# Mesh.net
KiCad netlist of a schematic drawn in EAGLE
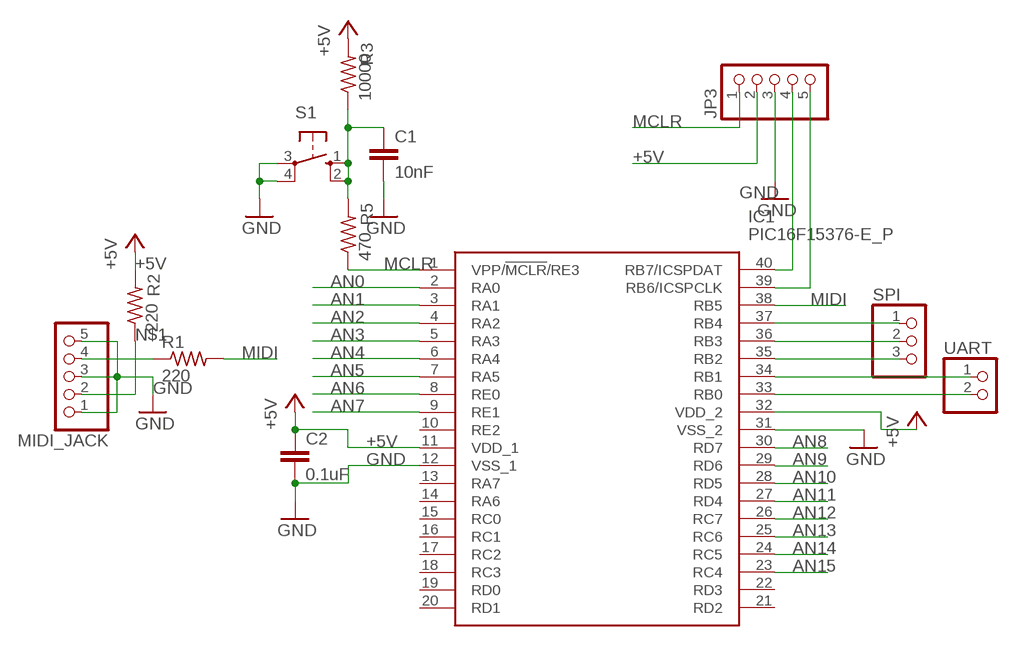
[diagram p0: schematic, sheet 1]
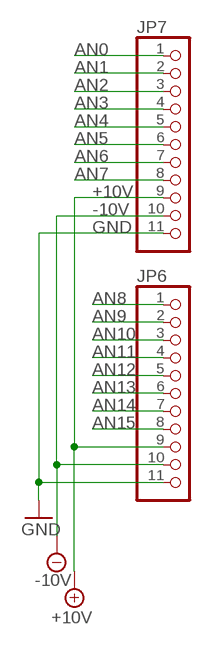
[diagram p1: schematic, sheet 2]
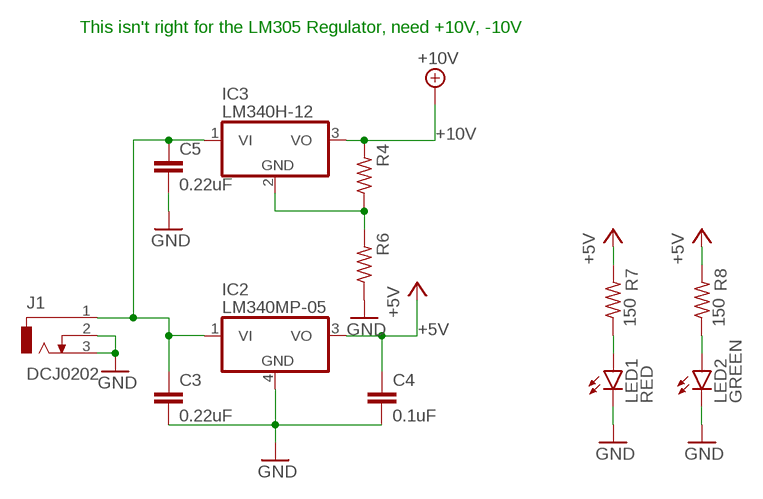
[diagram p2: schematic, sheet 3]
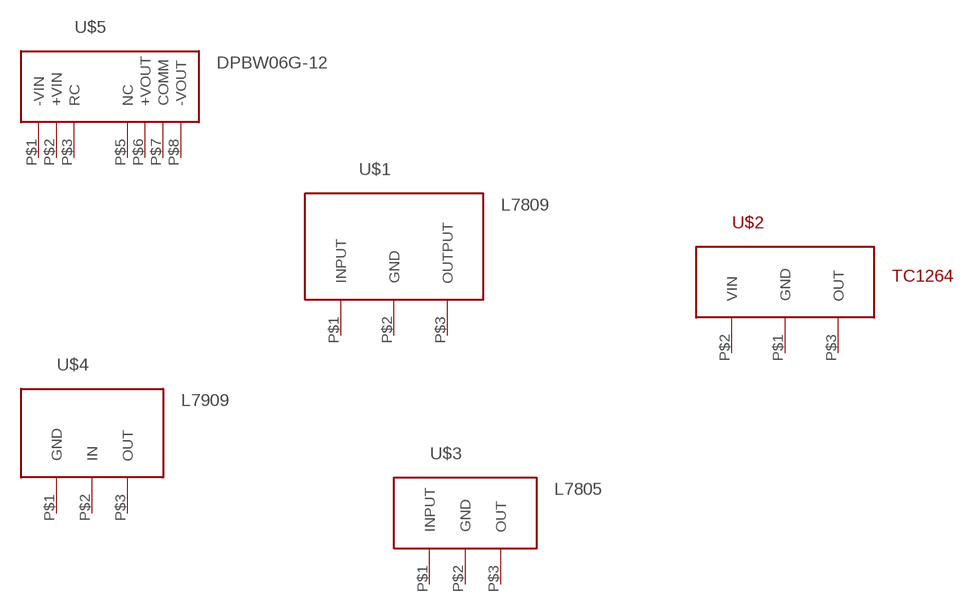
[diagram p3: schematic, sheet 4]

(export (version "E")
  (design (tool "Eeschema 10.0.6"))
  (components
    (comp (ref "JP6")
      (value "PINHD-1X11/90")
      (footprint "eagle-import:1X11_90")
      (libsource (lib "eagle-import") (part "PINHD-1X11/90"))
    )
    (comp (ref "JP7")
      (value "PINHD-1X11/90")
      (footprint "eagle-import:1X11_90")
      (libsource (lib "eagle-import") (part "PINHD-1X11/90"))
    )
    (comp (ref "U$1")
      (value "L7809")
      (footprint "eagle-import:L7809")
      (libsource (lib "eagle-import") (part "L7809"))
    )
    (comp (ref "U$2")
      (value "TC1264")
      (footprint "eagle-import:TC1264")
      (libsource (lib "eagle-import") (part "TC1264"))
    )
    (comp (ref "U$3")
      (value "L7805")
      (footprint "eagle-import:L7805")
      (libsource (lib "eagle-import") (part "L7805"))
    )
    (comp (ref "U$4")
      (value "L7909")
      (footprint "eagle-import:L7909")
      (libsource (lib "eagle-import") (part "L7909"))
    )
    (comp (ref "U$5")
      (value "DPBW06G-12")
      (footprint "eagle-import:DPBW06G-12")
      (libsource (lib "eagle-import") (part "DPBW06G-12"))
    )
    (comp (ref "C1")
      (value "10nF")
      (footprint "eagle-import:C0603")
      (libsource (lib "eagle-import") (part "C-EUC0603"))
    )
    (comp (ref "C2")
      (value "0.1uF")
      (footprint "eagle-import:C0603")
      (libsource (lib "eagle-import") (part "C-EUC0603"))
    )
    (comp (ref "IC1")
      (value "PIC16F15376-E_P")
      (footprint "eagle-import:DIP1543W58P254L5175H635Q40N")
      (fields
        (field (name "MANUFACTURER_PART_NUMBER") "PIC16F15376-E/P")
        (field (name "MOUSER_PART_NUMBER") "579-PIC16F15376-E/P")
      )
      (libsource (lib "eagle-import") (part "PIC16F15376-E_P"))
    )
    (comp (ref "JP3")
      (value "PINHD-1X5")
      (footprint "eagle-import:1X05")
      (libsource (lib "eagle-import") (part "PINHD-1X5"))
    )
    (comp (ref "MIDI_JACK")
      (value "PINHD-1X5")
      (footprint "eagle-import:1X05")
      (libsource (lib "eagle-import") (part "PINHD-1X5"))
    )
    (comp (ref "R1")
      (value "220")
      (footprint "eagle-import:R0603")
      (libsource (lib "eagle-import") (part "R-US_R0603"))
    )
    (comp (ref "R2")
      (value "220")
      (footprint "eagle-import:R0603")
      (libsource (lib "eagle-import") (part "R-US_R0603"))
    )
    (comp (ref "R3")
      (value "10000")
      (footprint "eagle-import:R0603")
      (libsource (lib "eagle-import") (part "R-US_R0603"))
    )
    (comp (ref "R5")
      (value "470")
      (footprint "eagle-import:R0603")
      (libsource (lib "eagle-import") (part "R-US_R0603"))
    )
    (comp (ref "S1")
      (value "10-XX")
      (footprint "eagle-import:B3F-10XX")
      (fields (field (name "MPN") "B3F-1000"))
      (libsource (lib "eagle-import") (part "10-XX"))
    )
    (comp (ref "SPI")
      (value "PINHD-1X3")
      (footprint "eagle-import:1X03")
      (libsource (lib "eagle-import") (part "PINHD-1X3"))
    )
    (comp (ref "UART")
      (value "PINHD-1X2")
      (footprint "eagle-import:1X02")
      (libsource (lib "eagle-import") (part "PINHD-1X2"))
    )
    (comp (ref "C3")
      (value "0.22uF")
      (footprint "eagle-import:C0603")
      (libsource (lib "eagle-import") (part "C-EUC0603"))
    )
    (comp (ref "C4")
      (value "0.1uF")
      (footprint "eagle-import:C0603")
      (libsource (lib "eagle-import") (part "C-EUC0603"))
    )
    (comp (ref "C5")
      (value "0.22uF")
      (footprint "eagle-import:C0603")
      (libsource (lib "eagle-import") (part "C-EUC0603"))
    )
    (comp (ref "IC2")
      (value "LM340MP-05")
      (footprint "eagle-import:SOT223")
      (libsource (lib "eagle-import") (part "LM340?-MP05"))
    )
    (comp (ref "IC3")
      (value "LM340H-12")
      (footprint "eagle-import:TO220H")
      (libsource (lib "eagle-import") (part "LM340?-H12"))
    )
    (comp (ref "J1")
      (value "DCJ0202")
      (footprint "eagle-import:DCJ0202")
      (libsource (lib "eagle-import") (part "DCJ0202"))
    )
    (comp (ref "LED1")
      (value "RED")
      (footprint "eagle-import:CHIP-LED0603")
      (libsource (lib "eagle-import") (part "LEDCHIP-LED0603"))
    )
    (comp (ref "LED2")
      (value "GREEN")
      (footprint "eagle-import:CHIP-LED0603")
      (libsource (lib "eagle-import") (part "LEDCHIP-LED0603"))
    )
    (comp (ref "R4")
      (value "R-US_R0603")
      (footprint "eagle-import:R0603")
      (libsource (lib "eagle-import") (part "R-US_R0603"))
    )
    (comp (ref "R6")
      (value "R-US_R0603")
      (footprint "eagle-import:R0603")
      (libsource (lib "eagle-import") (part "R-US_R0603"))
    )
    (comp (ref "R7")
      (value "150")
      (footprint "eagle-import:R0603")
      (libsource (lib "eagle-import") (part "R-US_R0603"))
    )
    (comp (ref "R8")
      (value "150")
      (footprint "eagle-import:R0603")
      (libsource (lib "eagle-import") (part "R-US_R0603"))
    )
  )
  (nets
    (net (code "1") (name "+5V") (class "Default")
      (node (ref "C2") (pin "1") (pinfunction "1_1") (pintype "passive"))
      (node (ref "C4") (pin "1") (pinfunction "1_1") (pintype "passive"))
      (node (ref "IC1") (pin "11") (pinfunction "VDD_1_11") (pintype "bidirectional"))
      (node (ref "IC1") (pin "32") (pinfunction "VDD_2_32") (pintype "bidirectional"))
      (node (ref "IC2") (pin "3") (pinfunction "VO_3") (pintype "passive"))
      (node (ref "JP3") (pin "2") (pinfunction "2_2") (pintype "passive"))
      (node (ref "R2") (pin "2") (pinfunction "2_2") (pintype "passive"))
      (node (ref "R3") (pin "2") (pinfunction "2_2") (pintype "passive"))
      (node (ref "R7") (pin "2") (pinfunction "2_2") (pintype "passive"))
      (node (ref "R8") (pin "2") (pinfunction "2_2") (pintype "passive"))
    )
    (net (code "2") (name "+10V") (class "Default")
      (node (ref "IC3") (pin "3") (pinfunction "VO_3") (pintype "passive"))
      (node (ref "JP6") (pin "9") (pinfunction "9_9") (pintype "passive"))
      (node (ref "JP7") (pin "9") (pinfunction "9_9") (pintype "passive"))
      (node (ref "R4") (pin "2") (pinfunction "2_2") (pintype "passive"))
    )
    (net (code "3") (name "-10V") (class "Default")
      (node (ref "JP6") (pin "10") (pinfunction "10_10") (pintype "passive"))
      (node (ref "JP7") (pin "10") (pinfunction "10_10") (pintype "passive"))
    )
    (net (code "4") (name "AN0") (class "Default")
      (node (ref "IC1") (pin "2") (pinfunction "RA0_2") (pintype "bidirectional"))
      (node (ref "JP7") (pin "1") (pinfunction "1_1") (pintype "passive"))
    )
    (net (code "5") (name "AN1") (class "Default")
      (node (ref "IC1") (pin "3") (pinfunction "RA1_3") (pintype "bidirectional"))
      (node (ref "JP7") (pin "2") (pinfunction "2_2") (pintype "passive"))
    )
    (net (code "6") (name "AN2") (class "Default")
      (node (ref "IC1") (pin "4") (pinfunction "RA2_4") (pintype "bidirectional"))
      (node (ref "JP7") (pin "3") (pinfunction "3_3") (pintype "passive"))
    )
    (net (code "7") (name "AN3") (class "Default")
      (node (ref "IC1") (pin "5") (pinfunction "RA3_5") (pintype "bidirectional"))
      (node (ref "JP7") (pin "4") (pinfunction "4_4") (pintype "passive"))
    )
    (net (code "8") (name "AN4") (class "Default")
      (node (ref "IC1") (pin "6") (pinfunction "RA4_6") (pintype "bidirectional"))
      (node (ref "JP7") (pin "5") (pinfunction "5_5") (pintype "passive"))
    )
    (net (code "9") (name "AN5") (class "Default")
      (node (ref "IC1") (pin "7") (pinfunction "RA5_7") (pintype "bidirectional"))
      (node (ref "JP7") (pin "6") (pinfunction "6_6") (pintype "passive"))
    )
    (net (code "10") (name "AN6") (class "Default")
      (node (ref "IC1") (pin "8") (pinfunction "RE0_8") (pintype "bidirectional"))
      (node (ref "JP7") (pin "7") (pinfunction "7_7") (pintype "passive"))
    )
    (net (code "11") (name "AN7") (class "Default")
      (node (ref "IC1") (pin "9") (pinfunction "RE1_9") (pintype "bidirectional"))
      (node (ref "JP7") (pin "8") (pinfunction "8_8") (pintype "passive"))
    )
    (net (code "12") (name "AN8") (class "Default")
      (node (ref "IC1") (pin "30") (pinfunction "RD7_30") (pintype "bidirectional"))
      (node (ref "JP6") (pin "1") (pinfunction "1_1") (pintype "passive"))
    )
    (net (code "13") (name "AN9") (class "Default")
      (node (ref "IC1") (pin "29") (pinfunction "RD6_29") (pintype "bidirectional"))
      (node (ref "JP6") (pin "2") (pinfunction "2_2") (pintype "passive"))
    )
    (net (code "14") (name "AN10") (class "Default")
      (node (ref "IC1") (pin "28") (pinfunction "RD5_28") (pintype "bidirectional"))
      (node (ref "JP6") (pin "3") (pinfunction "3_3") (pintype "passive"))
    )
    (net (code "15") (name "AN11") (class "Default")
      (node (ref "IC1") (pin "27") (pinfunction "RD4_27") (pintype "bidirectional"))
      (node (ref "JP6") (pin "4") (pinfunction "4_4") (pintype "passive"))
    )
    (net (code "16") (name "AN12") (class "Default")
      (node (ref "IC1") (pin "26") (pinfunction "RC7_26") (pintype "bidirectional"))
      (node (ref "JP6") (pin "5") (pinfunction "5_5") (pintype "passive"))
    )
    (net (code "17") (name "AN13") (class "Default")
      (node (ref "IC1") (pin "25") (pinfunction "RC6_25") (pintype "bidirectional"))
      (node (ref "JP6") (pin "6") (pinfunction "6_6") (pintype "passive"))
    )
    (net (code "18") (name "AN14") (class "Default")
      (node (ref "IC1") (pin "24") (pinfunction "RC5_24") (pintype "bidirectional"))
      (node (ref "JP6") (pin "7") (pinfunction "7_7") (pintype "passive"))
    )
    (net (code "19") (name "AN15") (class "Default")
      (node (ref "IC1") (pin "23") (pinfunction "RC4_23") (pintype "bidirectional"))
      (node (ref "JP6") (pin "8") (pinfunction "8_8") (pintype "passive"))
    )
    (net (code "20") (name "GND") (class "Default")
      (node (ref "C1") (pin "2") (pinfunction "2_2") (pintype "passive"))
      (node (ref "C2") (pin "2") (pinfunction "2_2") (pintype "passive"))
      (node (ref "C3") (pin "2") (pinfunction "2_2") (pintype "passive"))
      (node (ref "C4") (pin "2") (pinfunction "2_2") (pintype "passive"))
      (node (ref "C5") (pin "2") (pinfunction "2_2") (pintype "passive"))
      (node (ref "IC1") (pin "12") (pinfunction "VSS_1_12") (pintype "bidirectional"))
      (node (ref "IC1") (pin "31") (pinfunction "VSS_2_31") (pintype "bidirectional"))
      (node (ref "IC2") (pin "4") (pinfunction "GND_4") (pintype "passive"))
      (node (ref "J1") (pin "2") (pinfunction "2_2") (pintype "passive"))
      (node (ref "J1") (pin "3") (pinfunction "3_3") (pintype "passive"))
      (node (ref "JP3") (pin "3") (pinfunction "3_3") (pintype "passive"))
      (node (ref "JP6") (pin "11") (pinfunction "11_11") (pintype "passive"))
      (node (ref "JP7") (pin "11") (pinfunction "11_11") (pintype "passive"))
      (node (ref "LED1") (pin "C") (pinfunction "C_C") (pintype "passive"))
      (node (ref "LED2") (pin "C") (pinfunction "C_C") (pintype "passive"))
      (node (ref "MIDI_JACK") (pin "1") (pinfunction "1_1") (pintype "passive"))
      (node (ref "MIDI_JACK") (pin "3") (pinfunction "3_3") (pintype "passive"))
      (node (ref "MIDI_JACK") (pin "5") (pinfunction "5_5") (pintype "passive"))
      (node (ref "R6") (pin "1") (pinfunction "1_1") (pintype "passive"))
      (node (ref "S1") (pin "3") (pinfunction "P_3") (pintype "passive"))
      (node (ref "S1") (pin "4") (pinfunction "P1_4") (pintype "passive"))
    )
    (net (code "21") (name "MCLR") (class "Default")
      (node (ref "C1") (pin "1") (pinfunction "1_1") (pintype "passive"))
      (node (ref "IC1") (pin "1") (pinfunction "VPP/~{MCLR}/RE3_1") (pintype "bidirectional"))
      (node (ref "JP3") (pin "1") (pinfunction "1_1") (pintype "passive"))
      (node (ref "R3") (pin "1") (pinfunction "1_1") (pintype "passive"))
      (node (ref "R5") (pin "1") (pinfunction "1_1") (pintype "passive"))
      (node (ref "R5") (pin "2") (pinfunction "2_2") (pintype "passive"))
      (node (ref "S1") (pin "1") (pinfunction "S_1") (pintype "passive"))
      (node (ref "S1") (pin "2") (pinfunction "S1_2") (pintype "passive"))
    )
    (net (code "22") (name "MIDI") (class "Default")
      (node (ref "IC1") (pin "38") (pinfunction "RB5_38") (pintype "bidirectional"))
      (node (ref "R1") (pin "2") (pinfunction "2_2") (pintype "passive"))
    )
    (net (code "23") (name "N$1") (class "Default")
      (node (ref "MIDI_JACK") (pin "2") (pinfunction "2_2") (pintype "passive"))
      (node (ref "R2") (pin "1") (pinfunction "1_1") (pintype "passive"))
    )
    (net (code "24") (name "Net-(IC1-RB0)") (class "Default")
      (node (ref "IC1") (pin "33") (pinfunction "RB0_33") (pintype "bidirectional"))
      (node (ref "UART") (pin "2") (pinfunction "2_2") (pintype "passive"))
    )
    (net (code "25") (name "Net-(IC1-RB1)") (class "Default")
      (node (ref "IC1") (pin "34") (pinfunction "RB1_34") (pintype "bidirectional"))
      (node (ref "UART") (pin "1") (pinfunction "1_1") (pintype "passive"))
    )
    (net (code "26") (name "Net-(IC1-RB2)") (class "Default")
      (node (ref "IC1") (pin "35") (pinfunction "RB2_35") (pintype "bidirectional"))
      (node (ref "SPI") (pin "3") (pinfunction "3_3") (pintype "passive"))
    )
    (net (code "27") (name "Net-(IC1-RB3)") (class "Default")
      (node (ref "IC1") (pin "36") (pinfunction "RB3_36") (pintype "bidirectional"))
      (node (ref "SPI") (pin "2") (pinfunction "2_2") (pintype "passive"))
    )
    (net (code "28") (name "Net-(IC1-RB4)") (class "Default")
      (node (ref "IC1") (pin "37") (pinfunction "RB4_37") (pintype "bidirectional"))
      (node (ref "SPI") (pin "1") (pinfunction "1_1") (pintype "passive"))
    )
    (net (code "29") (name "Net-(IC1-RB6{slash}ICSPCLK)") (class "Default")
      (node (ref "IC1") (pin "39") (pinfunction "RB6/ICSPCLK_39") (pintype "bidirectional"))
      (node (ref "JP3") (pin "5") (pinfunction "5_5") (pintype "passive"))
    )
    (net (code "30") (name "Net-(IC1-RB7{slash}ICSPDAT)") (class "Default")
      (node (ref "IC1") (pin "40") (pinfunction "RB7/ICSPDAT_40") (pintype "bidirectional"))
      (node (ref "JP3") (pin "4") (pinfunction "4_4") (pintype "passive"))
    )
    (net (code "31") (name "Net-(IC2-VI)") (class "Default")
      (node (ref "C3") (pin "1") (pinfunction "1_1") (pintype "passive"))
      (node (ref "C5") (pin "1") (pinfunction "1_1") (pintype "passive"))
      (node (ref "IC2") (pin "1") (pinfunction "VI_1") (pintype "input"))
      (node (ref "IC3") (pin "1") (pinfunction "VI_1") (pintype "input"))
      (node (ref "J1") (pin "1") (pinfunction "1_1") (pintype "passive"))
    )
    (net (code "32") (name "Net-(IC3-GND)") (class "Default")
      (node (ref "IC3") (pin "2") (pinfunction "GND_2") (pintype "passive"))
      (node (ref "R4") (pin "1") (pinfunction "1_1") (pintype "passive"))
      (node (ref "R6") (pin "2") (pinfunction "2_2") (pintype "passive"))
    )
    (net (code "33") (name "Net-(LED1-PadA)") (class "Default")
      (node (ref "LED1") (pin "A") (pinfunction "A_A") (pintype "passive"))
      (node (ref "R7") (pin "1") (pinfunction "1_1") (pintype "passive"))
    )
    (net (code "34") (name "Net-(LED2-PadA)") (class "Default")
      (node (ref "LED2") (pin "A") (pinfunction "A_A") (pintype "passive"))
      (node (ref "R8") (pin "1") (pinfunction "1_1") (pintype "passive"))
    )
    (net (code "35") (name "Net-(MIDI_JACK-Pad4)") (class "Default")
      (node (ref "MIDI_JACK") (pin "4") (pinfunction "4_4") (pintype "passive"))
      (node (ref "R1") (pin "1") (pinfunction "1_1") (pintype "passive"))
    )
    (net (code "36") (name "unconnected-(IC1-RA6-Pad14)") (class "Default")
      (node (ref "IC1") (pin "14") (pinfunction "RA6_14") (pintype "bidirectional"))
    )
    (net (code "37") (name "unconnected-(IC1-RA7-Pad13)") (class "Default")
      (node (ref "IC1") (pin "13") (pinfunction "RA7_13") (pintype "bidirectional"))
    )
    (net (code "38") (name "unconnected-(IC1-RC0-Pad15)") (class "Default")
      (node (ref "IC1") (pin "15") (pinfunction "RC0_15") (pintype "bidirectional"))
    )
    (net (code "39") (name "unconnected-(IC1-RC1-Pad16)") (class "Default")
      (node (ref "IC1") (pin "16") (pinfunction "RC1_16") (pintype "bidirectional"))
    )
    (net (code "40") (name "unconnected-(IC1-RC2-Pad17)") (class "Default")
      (node (ref "IC1") (pin "17") (pinfunction "RC2_17") (pintype "bidirectional"))
    )
    (net (code "41") (name "unconnected-(IC1-RC3-Pad18)") (class "Default")
      (node (ref "IC1") (pin "18") (pinfunction "RC3_18") (pintype "bidirectional"))
    )
    (net (code "42") (name "unconnected-(IC1-RD0-Pad19)") (class "Default")
      (node (ref "IC1") (pin "19") (pinfunction "RD0_19") (pintype "bidirectional"))
    )
    (net (code "43") (name "unconnected-(IC1-RD1-Pad20)") (class "Default")
      (node (ref "IC1") (pin "20") (pinfunction "RD1_20") (pintype "bidirectional"))
    )
    (net (code "44") (name "unconnected-(IC1-RD2-Pad21)") (class "Default")
      (node (ref "IC1") (pin "21") (pinfunction "RD2_21") (pintype "bidirectional"))
    )
    (net (code "45") (name "unconnected-(IC1-RD3-Pad22)") (class "Default")
      (node (ref "IC1") (pin "22") (pinfunction "RD3_22") (pintype "bidirectional"))
    )
    (net (code "46") (name "unconnected-(IC1-RE2-Pad10)") (class "Default")
      (node (ref "IC1") (pin "10") (pinfunction "RE2_10") (pintype "bidirectional"))
    )
    (net (code "47") (name "unconnected-(U$1-GND-PadP$2)") (class "Default")
      (node (ref "U$1") (pin "P$2") (pinfunction "GND_P$2") (pintype "bidirectional"))
    )
    (net (code "48") (name "unconnected-(U$1-INPUT-PadP$1)") (class "Default")
      (node (ref "U$1") (pin "P$1") (pinfunction "INPUT_P$1") (pintype "bidirectional"))
    )
    (net (code "49") (name "unconnected-(U$1-OUTPUT-PadP$3)") (class "Default")
      (node (ref "U$1") (pin "P$3") (pinfunction "OUTPUT_P$3") (pintype "bidirectional"))
    )
    (net (code "50") (name "unconnected-(U$2-GND-PadP$1)") (class "Default")
      (node (ref "U$2") (pin "P$1") (pinfunction "GND_P$1") (pintype "bidirectional"))
    )
    (net (code "51") (name "unconnected-(U$2-OUT-PadP$3)") (class "Default")
      (node (ref "U$2") (pin "P$3") (pinfunction "OUT_P$3") (pintype "bidirectional"))
    )
    (net (code "52") (name "unconnected-(U$2-VIN-PadP$2)") (class "Default")
      (node (ref "U$2") (pin "P$2") (pinfunction "VIN_P$2") (pintype "bidirectional"))
    )
    (net (code "53") (name "unconnected-(U$3-GND-PadP$2)") (class "Default")
      (node (ref "U$3") (pin "P$2") (pinfunction "GND_P$2") (pintype "bidirectional"))
    )
    (net (code "54") (name "unconnected-(U$3-INPUT-PadP$1)") (class "Default")
      (node (ref "U$3") (pin "P$1") (pinfunction "INPUT_P$1") (pintype "bidirectional"))
    )
    (net (code "55") (name "unconnected-(U$3-OUT-PadP$3)") (class "Default")
      (node (ref "U$3") (pin "P$3") (pinfunction "OUT_P$3") (pintype "bidirectional"))
    )
    (net (code "56") (name "unconnected-(U$4-GND-PadP$1)") (class "Default")
      (node (ref "U$4") (pin "P$1") (pinfunction "GND_P$1") (pintype "bidirectional"))
    )
    (net (code "57") (name "unconnected-(U$4-IN-PadP$2)") (class "Default")
      (node (ref "U$4") (pin "P$2") (pinfunction "IN_P$2") (pintype "bidirectional"))
    )
    (net (code "58") (name "unconnected-(U$4-OUT-PadP$3)") (class "Default")
      (node (ref "U$4") (pin "P$3") (pinfunction "OUT_P$3") (pintype "bidirectional"))
    )
    (net (code "59") (name "unconnected-(U$5-+VIN-PadP$2)") (class "Default")
      (node (ref "U$5") (pin "P$2") (pinfunction "+VIN_P$2") (pintype "bidirectional"))
    )
    (net (code "60") (name "unconnected-(U$5-+VOUT-PadP$6)") (class "Default")
      (node (ref "U$5") (pin "P$6") (pinfunction "+VOUT_P$6") (pintype "bidirectional"))
    )
    (net (code "61") (name "unconnected-(U$5--VIN-PadP$1)") (class "Default")
      (node (ref "U$5") (pin "P$1") (pinfunction "-VIN_P$1") (pintype "bidirectional"))
    )
    (net (code "62") (name "unconnected-(U$5--VOUT-PadP$8)") (class "Default")
      (node (ref "U$5") (pin "P$8") (pinfunction "-VOUT_P$8") (pintype "bidirectional"))
    )
    (net (code "63") (name "unconnected-(U$5-COMM-PadP$7)") (class "Default")
      (node (ref "U$5") (pin "P$7") (pinfunction "COMM_P$7") (pintype "bidirectional"))
    )
    (net (code "64") (name "unconnected-(U$5-NC-PadP$5)") (class "Default")
      (node (ref "U$5") (pin "P$5") (pinfunction "NC_P$5") (pintype "bidirectional"))
    )
    (net (code "65") (name "unconnected-(U$5-RC-PadP$3)") (class "Default")
      (node (ref "U$5") (pin "P$3") (pinfunction "RC_P$3") (pintype "bidirectional"))
    )
  )
)
